# USB-UART.net
KiCad netlist of a schematic drawn in Altium Designer
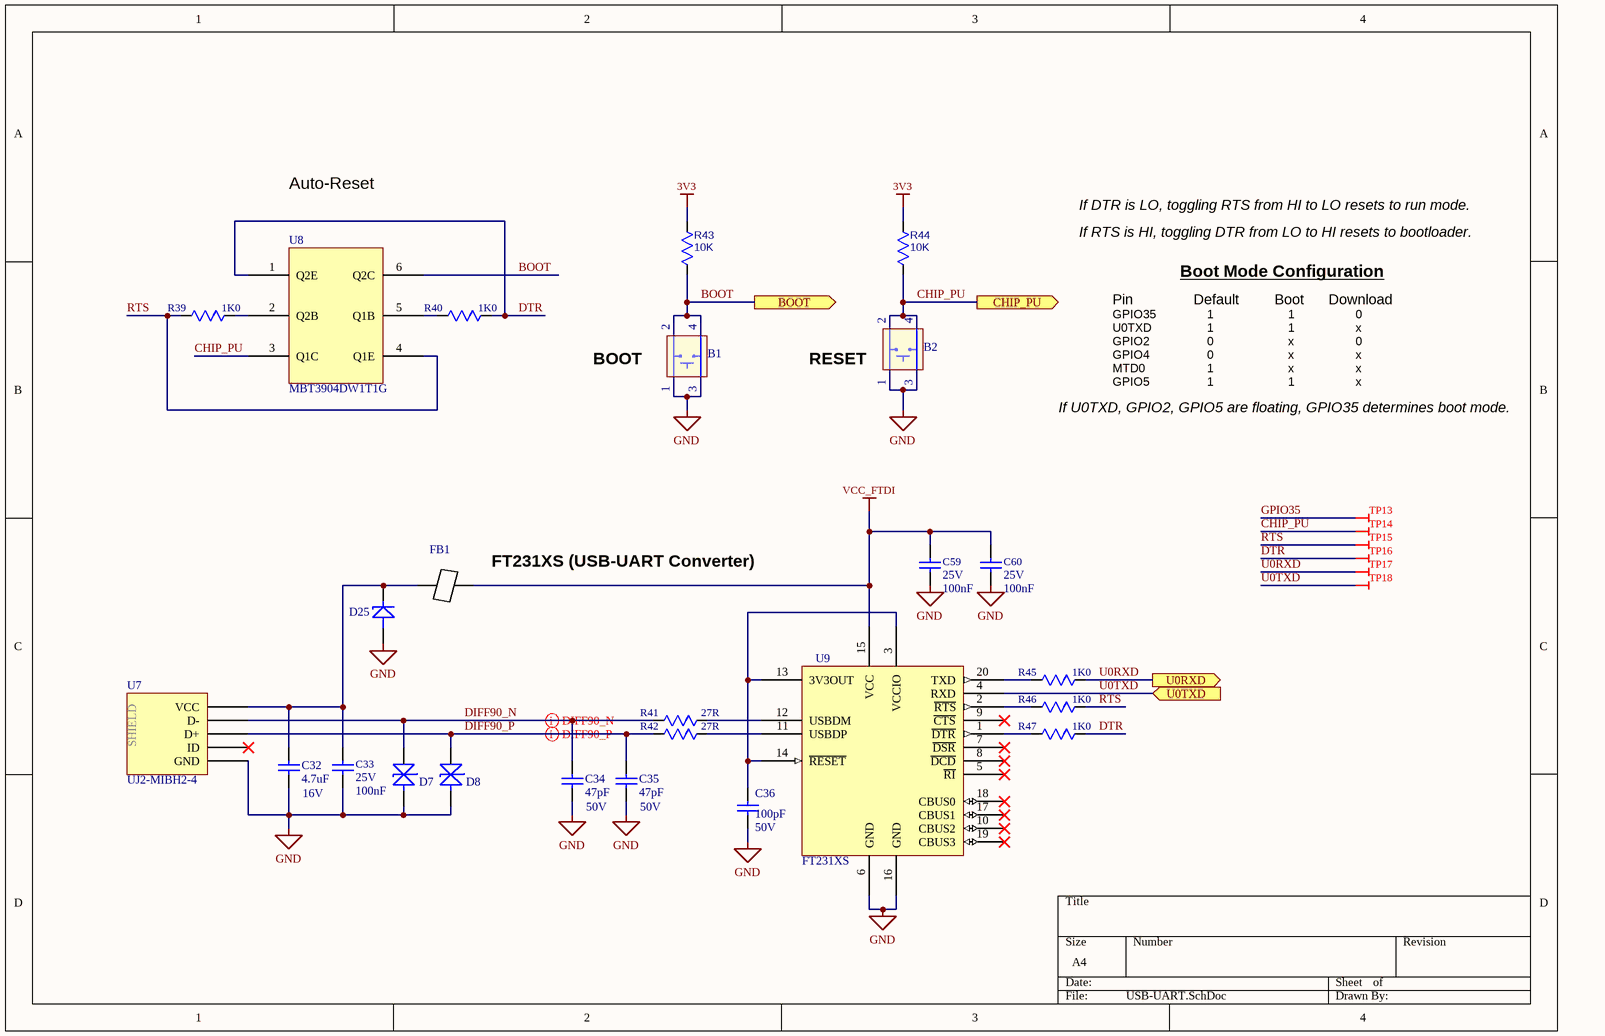
[diagram p0: USB-UART.SchDoc]

(export (version "E")
  (design (tool "Eeschema 10.0.6"))
  (components
    (comp (ref "B1")
      (value "Button C&K PTS815 SJG 250 SMTR LFS")
      (footprint "PTS 815")
      (description "Push Button Top")
      (fields
        (field (name "MANUFACTURER") "C&K Components")
        (field (name "MANUFACTURER PART NUMBER") "PTS815 SJG 250 SMTR LFS")
      )
      (libsource (lib "Connectors") (part "Button C&K PTS815 SJG 250 SMTR LFS"))
    )
    (comp (ref "B2")
      (value "Button C&K PTS815 SJG 250 SMTR LFS")
      (footprint "PTS 815")
      (description "Push Button Top")
      (fields
        (field (name "MANUFACTURER") "C&K Components")
        (field (name "MANUFACTURER PART NUMBER") "PTS815 SJG 250 SMTR LFS")
      )
      (libsource (lib "Connectors") (part "Button C&K PTS815 SJG 250 SMTR LFS"))
    )
    (comp (ref "C32")
      (value "4.7uF")
      (footprint "C1005[0402]")
      (description "Cap,4.7uF,10V,20%,X5R,0402")
      (fields
        (field (name "MANUFACTURER") "Samsung Electro-Mechanics")
        (field (name "MANUFACTURER PART NUMBER") "CL05A475MO5NUNC")
        (field (name "VOLTAGE") "16V")
      )
      (libsource (lib "Capacitors") (part "4.7uF_0402_10V"))
    )
    (comp (ref "C33")
      (value "100nF")
      (footprint "CAPC1005X06N")
      (fields
        (field (name "VOLTAGE") "25V")
        (field (name "MANUFACTURER PART NUMBER") "CL05A104KA5NNNC")
        (field (name "MANUFACTURER") "Samsung")
        (field (name "Comment") "4.7uF")
      )
      (libsource (lib "Capacitors") (part "4.7uF_0603_10V"))
    )
    (comp (ref "C34")
      (value "47pF")
      (footprint "C1005[0402]")
      (description "Cap,47pF,50V,5%,C0G/NP0")
      (fields
        (field (name "MANUFACTURER") "Yageo")
        (field (name "MANUFACTURER PART NUMBER") "CC0402JRNPO9BN470")
        (field (name "VOLTAGE") "50V")
      )
      (libsource (lib "Capacitors") (part "47pF_0402_50V"))
    )
    (comp (ref "C35")
      (value "47pF")
      (footprint "C1005[0402]")
      (description "Cap,47pF,50V,5%,C0G/NP0")
      (fields
        (field (name "MANUFACTURER PART NUMBER") "CC0402JRNPO9BN470")
        (field (name "MANUFACTURER") "Yageo")
        (field (name "VOLTAGE") "50V")
      )
      (libsource (lib "Capacitors") (part "47pF_0402_50V"))
    )
    (comp (ref "C36")
      (value "100pF")
      (footprint "C1005[0402]")
      (description "Cap,100pF,10V,5%,C0G/NP0,0402")
      (fields
        (field (name "MANUFACTURER PART NUMBER") "CC0402JRNPO9BN101")
        (field (name "MANUFACTURER") "Yageo")
        (field (name "VOLTAGE") "50V")
      )
      (libsource (lib "Capacitors") (part "100pF_0402_10V"))
    )
    (comp (ref "C59")
      (value "100nF")
      (footprint "CAPC1005X06N")
      (fields
        (field (name "VOLTAGE") "25V")
        (field (name "MANUFACTURER PART NUMBER") "CL05A104KA5NNNC")
        (field (name "MANUFACTURER") "Samsung")
        (field (name "Comment") "4.7uF")
      )
      (libsource (lib "Capacitors") (part "4.7uF_0603_10V"))
    )
    (comp (ref "C60")
      (value "100nF")
      (footprint "CAPC1005X06N")
      (fields
        (field (name "VOLTAGE") "25V")
        (field (name "MANUFACTURER PART NUMBER") "CL05A104KA5NNNC")
        (field (name "MANUFACTURER") "Samsung")
        (field (name "Comment") "4.7uF")
      )
      (libsource (lib "Capacitors") (part "4.7uF_0603_10V"))
    )
    (comp (ref "D7")
      (value "ESD7951ST5GOSCT-ND")
      (footprint "SODFL100X40-2N")
      (description "TVS Diode")
      (fields
        (field (name "MANUFACTURER") "ON Semiconductor")
        (field (name "MANUFACTURER PART NUMBER") "ESD7951ST5G")
      )
      (libsource (lib "Gas Monitor Components") (part "ESD7951S"))
    )
    (comp (ref "D8")
      (value "ESD7951ST5GOSCT-ND")
      (footprint "SODFL100X40-2N")
      (description "TVS Diode")
      (fields
        (field (name "MANUFACTURER") "ON Semiconductor")
        (field (name "MANUFACTURER PART NUMBER") "ESD7951ST5G")
      )
      (libsource (lib "Gas Monitor Components") (part "ESD7951S"))
    )
    (comp (ref "D25")
      (value "5V TVS")
      (footprint "NXP PTVSxS1UR-Series (SOD123W)")
      (fields
        (field (name "MANUFACTURER") "Nexperia")
        (field (name "MANUFACTURER PART NUMBER") "PTVS5V0S1UR,115")
      )
      (libsource (lib "FSM_2018") (part "NXP PTVSxS1UR-Series"))
    )
    (comp (ref "FB1")
      (value "Ferrite Bead")
      (footprint "MI0805K400R-10")
      (description "MI0805K400R-10")
      (fields (field (name "MANUFACTURER") "Laird"))
      (libsource (lib "Gas Monitor Components") (part "Ferrite Bead"))
    )
    (comp (ref "R39")
      (value "1K0")
      (footprint "RESC1005X03N")
      (description "RES 1K Ohm ±5%, 0.25W,1/4W 0603")
      (fields
        (field (name "MANUFACTURER") "Panasonic")
        (field (name "MANUFACTURER PART NUMBER") "ERJ-2RKF1001X")
      )
      (libsource (lib "Resistors") (part "1K00_0603_0.1W"))
    )
    (comp (ref "R40")
      (value "1K0")
      (footprint "RESC1005X03N")
      (description "RES 1K Ohm ±5%, 0.25W,1/4W 0603")
      (fields
        (field (name "MANUFACTURER") "Panasonic")
        (field (name "MANUFACTURER PART NUMBER") "ERJ-2RKF1001X")
      )
      (libsource (lib "Resistors") (part "1K00_0603_0.1W"))
    )
    (comp (ref "R41")
      (value "27R")
      (footprint "RESC1005X03N")
      (description "RES 1K Ohm ±5%, 0.25W,1/4W 0603")
      (fields
        (field (name "MANUFACTURER") "Panasonic")
        (field (name "MANUFACTURER PART NUMBER") "ERJ-2GEJ270X")
      )
      (libsource (lib "Resistors") (part "1K00_0603_0.1W"))
    )
    (comp (ref "R42")
      (value "27R")
      (footprint "RESC1005X03N")
      (description "RES 1K Ohm ±5%, 0.25W,1/4W 0603")
      (fields
        (field (name "MANUFACTURER") "Panasonic")
        (field (name "MANUFACTURER PART NUMBER") "ERJ-2GEJ270X")
      )
      (libsource (lib "Resistors") (part "1K00_0603_0.1W"))
    )
    (comp (ref "R43")
      (value "10K")
      (footprint "RESC1005X03N")
      (description "RES 1K Ohm ±5%, 0.25W,1/4W 0603")
      (fields
        (field (name "MANUFACTURER") "Panasonic")
        (field (name "MANUFACTURER PART NUMBER") "ERJ-2RKF1002X")
      )
      (libsource (lib "Resistors") (part "1K00_0603_0.1W"))
    )
    (comp (ref "R44")
      (value "10K")
      (footprint "RESC1005X03N")
      (description "RES 1K Ohm ±5%, 0.25W,1/4W 0603")
      (fields
        (field (name "MANUFACTURER") "Panasonic")
        (field (name "MANUFACTURER PART NUMBER") "ERJ-2RKF1002X")
      )
      (libsource (lib "Resistors") (part "1K00_0603_0.1W"))
    )
    (comp (ref "R45")
      (value "1K0")
      (footprint "RESC1005X03N")
      (description "RES 1K Ohm ±5%, 0.25W,1/4W 0603")
      (fields
        (field (name "MANUFACTURER") "Panasonic")
        (field (name "MANUFACTURER PART NUMBER") "ERJ-2RKF1001X")
      )
      (libsource (lib "Resistors") (part "1K00_0603_0.1W"))
    )
    (comp (ref "R46")
      (value "1K0")
      (footprint "RESC1005X03N")
      (description "RES 1K Ohm ±5%, 0.25W,1/4W 0603")
      (fields
        (field (name "MANUFACTURER") "Panasonic")
        (field (name "MANUFACTURER PART NUMBER") "ERJ-2RKF1001X")
      )
      (libsource (lib "Resistors") (part "1K00_0603_0.1W"))
    )
    (comp (ref "R47")
      (value "1K0")
      (footprint "RESC1005X03N")
      (description "RES 1K Ohm ±5%, 0.25W,1/4W 0603")
      (fields
        (field (name "MANUFACTURER") "Panasonic")
        (field (name "MANUFACTURER PART NUMBER") "ERJ-2RKF1001X")
      )
      (libsource (lib "Resistors") (part "1K00_0603_0.1W"))
    )
    (comp (ref "TP13")
      (value "PAD")
      (footprint "TP_SMD_39MIL")
      (description "SMD Test Pad")
      (fields (field (name "MANUFACTURER") "No P/N Required"))
      (libsource (lib "Connectors") (part "TP_SMD_39MIL"))
    )
    (comp (ref "TP14")
      (value "PAD")
      (footprint "TP_SMD_39MIL")
      (description "SMD Test Pad")
      (fields (field (name "MANUFACTURER") "No P/N Required"))
      (libsource (lib "Connectors") (part "TP_SMD_39MIL"))
    )
    (comp (ref "TP15")
      (value "PAD")
      (footprint "TP_SMD_39MIL")
      (description "SMD Test Pad")
      (fields (field (name "MANUFACTURER") "No P/N Required"))
      (libsource (lib "Connectors") (part "TP_SMD_39MIL"))
    )
    (comp (ref "TP16")
      (value "PAD")
      (footprint "TP_SMD_39MIL")
      (description "SMD Test Pad")
      (fields (field (name "MANUFACTURER") "No P/N Required"))
      (libsource (lib "Connectors") (part "TP_SMD_39MIL"))
    )
    (comp (ref "TP17")
      (value "PAD")
      (footprint "TP_SMD_39MIL")
      (description "SMD Test Pad")
      (fields (field (name "MANUFACTURER") "No P/N Required"))
      (libsource (lib "Connectors") (part "TP_SMD_39MIL"))
    )
    (comp (ref "TP18")
      (value "PAD")
      (footprint "TP_SMD_39MIL")
      (description "SMD Test Pad")
      (fields (field (name "MANUFACTURER") "No P/N Required"))
      (libsource (lib "Connectors") (part "TP_SMD_39MIL"))
    )
    (comp (ref "U7")
      (value "UJ2-MIBH2-4")
      (footprint "UJ2-MIBH2-4-SMT")
      (fields
        (field (name "MANUFACTURER") "CUI")
        (field (name "MANUFACTURER PART NUMBER") "UJ2-MIBH2-4-SMT-TR")
      )
      (libsource (lib "Gas Monitor Components") (part "USB Shield"))
    )
    (comp (ref "U8")
      (value "MBT3904DW1T1G")
      (footprint "SOT65P210X110-6N")
      (description "Dual NPN Transistors")
      (fields
        (field (name "MANUFACTURER") "ON Semiconductor")
        (field (name "MANUFACTURER PART NUMBER") "SMBT3904DW1T1G")
      )
      (libsource (lib "Gas Monitor Components") (part "MBT3904DW1"))
    )
    (comp (ref "U9")
      (value "FT231XS")
      (footprint "SOP64P1030X175-20N")
      (description "USB-UART Interface")
      (fields (field (name "MANUFACTURER") "FTDI") (field (name "MANUFACTURER PART NUMBER") "FT231XS-R"))
      (libsource (lib "Gas Monitor Components") (part "FT231XS"))
    )
  )
  (nets
    (net (code "1") (name "/BOOT") (class "Default")
      (node (ref "B1") (pin "2") (pinfunction "2_2") (pintype "passive"))
      (node (ref "B1") (pin "4") (pinfunction "4_4") (pintype "passive"))
      (node (ref "R43") (pin "1") (pintype "passive"))
      (node (ref "U8") (pin "6") (pinfunction "Q2C_6") (pintype "passive"))
    )
    (net (code "2") (name "/CHIP_PU") (class "Default")
      (node (ref "B2") (pin "2") (pinfunction "2_2") (pintype "passive"))
      (node (ref "B2") (pin "4") (pinfunction "4_4") (pintype "passive"))
      (node (ref "R44") (pin "1") (pintype "passive"))
      (node (ref "TP14") (pin "1") (pintype "passive"))
      (node (ref "U8") (pin "3") (pinfunction "Q1C_3") (pintype "passive"))
    )
    (net (code "3") (name "/DIFF90_N") (class "Default")
      (node (ref "C34") (pin "2") (pintype "passive"))
      (node (ref "D7") (pin "2") (pinfunction "ANODE_2") (pintype "passive"))
      (node (ref "R41") (pin "2") (pintype "passive"))
      (node (ref "U7") (pin "2") (pinfunction "D-_2") (pintype "passive"))
    )
    (net (code "4") (name "/DIFF90_P") (class "Default")
      (node (ref "C35") (pin "2") (pintype "passive"))
      (node (ref "D8") (pin "2") (pinfunction "ANODE_2") (pintype "passive"))
      (node (ref "R42") (pin "2") (pintype "passive"))
      (node (ref "U7") (pin "3") (pinfunction "D+_3") (pintype "passive"))
    )
    (net (code "5") (name "/DTR") (class "Default")
      (node (ref "R40") (pin "2") (pintype "passive"))
      (node (ref "R47") (pin "2") (pintype "passive"))
      (node (ref "TP16") (pin "1") (pintype "passive"))
      (node (ref "U8") (pin "1") (pinfunction "Q2E_1") (pintype "passive"))
    )
    (net (code "6") (name "/GPIO35") (class "Default") (node (ref "TP13") (pin "1") (pintype "passive")))
    (net (code "7") (name "/RTS") (class "Default")
      (node (ref "R39") (pin "1") (pintype "passive"))
      (node (ref "R46") (pin "2") (pintype "passive"))
      (node (ref "TP15") (pin "1") (pintype "passive"))
      (node (ref "U8") (pin "4") (pinfunction "Q1E_4") (pintype "passive"))
    )
    (net (code "8") (name "/U0RXD") (class "Default")
      (node (ref "R45") (pin "2") (pintype "passive"))
      (node (ref "TP17") (pin "1") (pintype "passive"))
    )
    (net (code "9") (name "/U0TXD") (class "Default")
      (node (ref "TP18") (pin "1") (pintype "passive"))
      (node (ref "U9") (pin "4") (pinfunction "RXD_4") (pintype "passive"))
    )
    (net (code "10") (name "3V3") (class "Default")
      (node (ref "R43") (pin "2") (pintype "passive"))
      (node (ref "R44") (pin "2") (pintype "passive"))
    )
    (net (code "11") (name "GND") (class "Default")
      (node (ref "B1") (pin "1") (pinfunction "1_1") (pintype "passive"))
      (node (ref "B1") (pin "3") (pinfunction "3_3") (pintype "passive"))
      (node (ref "B2") (pin "1") (pinfunction "1_1") (pintype "passive"))
      (node (ref "B2") (pin "3") (pinfunction "3_3") (pintype "passive"))
      (node (ref "C32") (pin "1") (pintype "passive"))
      (node (ref "C33") (pin "2") (pintype "passive"))
      (node (ref "C34") (pin "1") (pintype "passive"))
      (node (ref "C35") (pin "1") (pintype "passive"))
      (node (ref "C36") (pin "1") (pintype "passive"))
      (node (ref "C59") (pin "2") (pintype "passive"))
      (node (ref "C60") (pin "2") (pintype "passive"))
      (node (ref "D25") (pin "2") (pinfunction "2_2") (pintype "passive"))
      (node (ref "D7") (pin "1") (pinfunction "CATHODE_1") (pintype "passive"))
      (node (ref "D8") (pin "1") (pinfunction "CATHODE_1") (pintype "passive"))
      (node (ref "U7") (pin "5") (pinfunction "GND_5") (pintype "power_in"))
      (node (ref "U9") (pin "16") (pinfunction "GND_16") (pintype "power_in"))
      (node (ref "U9") (pin "6") (pinfunction "GND_6") (pintype "power_in"))
    )
    (net (code "12") (name "Net-(U7-VCC)") (class "Default")
      (node (ref "C32") (pin "2") (pintype "passive"))
      (node (ref "C33") (pin "1") (pintype "passive"))
      (node (ref "D25") (pin "1") (pinfunction "1_1") (pintype "passive"))
      (node (ref "FB1") (pin "1") (pinfunction "1_1") (pintype "passive"))
      (node (ref "U7") (pin "1") (pinfunction "VCC_1") (pintype "power_in"))
    )
    (net (code "13") (name "Net-(U8-Q1B)") (class "Default")
      (node (ref "R40") (pin "1") (pintype "passive"))
      (node (ref "U8") (pin "5") (pinfunction "Q1B_5") (pintype "passive"))
    )
    (net (code "14") (name "Net-(U8-Q2B)") (class "Default")
      (node (ref "R39") (pin "2") (pintype "passive"))
      (node (ref "U8") (pin "2") (pinfunction "Q2B_2") (pintype "passive"))
    )
    (net (code "15") (name "Net-(U9-3V3OUT)") (class "Default")
      (node (ref "C36") (pin "2") (pintype "passive"))
      (node (ref "U9") (pin "13") (pinfunction "3V3OUT_13") (pintype "power_in"))
      (node (ref "U9") (pin "14") (pinfunction "~{RESET}_14") (pintype "input"))
      (node (ref "U9") (pin "3") (pinfunction "VCCIO_3") (pintype "passive"))
    )
    (net (code "16") (name "Net-(U9-TXD)") (class "Default")
      (node (ref "R45") (pin "1") (pintype "passive"))
      (node (ref "U9") (pin "20") (pinfunction "TXD_20") (pintype "output"))
    )
    (net (code "17") (name "Net-(U9-USBDM)") (class "Default")
      (node (ref "R41") (pin "1") (pintype "passive"))
      (node (ref "U9") (pin "12") (pinfunction "USBDM_12") (pintype "passive"))
    )
    (net (code "18") (name "Net-(U9-USBDP)") (class "Default")
      (node (ref "R42") (pin "1") (pintype "passive"))
      (node (ref "U9") (pin "11") (pinfunction "USBDP_11") (pintype "passive"))
    )
    (net (code "19") (name "Net-(U9-~{DTR})") (class "Default")
      (node (ref "R47") (pin "1") (pintype "passive"))
      (node (ref "U9") (pin "1") (pinfunction "~{DTR}_1") (pintype "output"))
    )
    (net (code "20") (name "Net-(U9-~{RTS})") (class "Default")
      (node (ref "R46") (pin "1") (pintype "passive"))
      (node (ref "U9") (pin "2") (pinfunction "~{RTS}_2") (pintype "output"))
    )
    (net (code "21") (name "VCC_FTDI") (class "Default")
      (node (ref "C59") (pin "1") (pintype "passive"))
      (node (ref "C60") (pin "1") (pintype "passive"))
      (node (ref "FB1") (pin "2") (pinfunction "2_2") (pintype "passive"))
      (node (ref "U9") (pin "15") (pinfunction "VCC_15") (pintype "power_in"))
    )
    (net (code "22") (name "unconnected-(U7-ID-Pad4)") (class "Default")
      (node (ref "U7") (pin "4") (pinfunction "ID_4") (pintype "passive+no_connect"))
    )
    (net (code "23") (name "unconnected-(U9-CBUS0-Pad18)") (class "Default")
      (node (ref "U9") (pin "18") (pinfunction "CBUS0_18") (pintype "bidirectional+no_connect"))
    )
    (net (code "24") (name "unconnected-(U9-CBUS1-Pad17)") (class "Default")
      (node (ref "U9") (pin "17") (pinfunction "CBUS1_17") (pintype "bidirectional+no_connect"))
    )
    (net (code "25") (name "unconnected-(U9-CBUS2-Pad10)") (class "Default")
      (node (ref "U9") (pin "10") (pinfunction "CBUS2_10") (pintype "bidirectional+no_connect"))
    )
    (net (code "26") (name "unconnected-(U9-CBUS3-Pad19)") (class "Default")
      (node (ref "U9") (pin "19") (pinfunction "CBUS3_19") (pintype "bidirectional+no_connect"))
    )
    (net (code "27") (name "unconnected-(U9-~{CTS}-Pad9)") (class "Default")
      (node (ref "U9") (pin "9") (pinfunction "~{CTS}_9") (pintype "passive+no_connect"))
    )
    (net (code "28") (name "unconnected-(U9-~{DCD}-Pad8)") (class "Default")
      (node (ref "U9") (pin "8") (pinfunction "~{DCD}_8") (pintype "passive+no_connect"))
    )
    (net (code "29") (name "unconnected-(U9-~{DSR}-Pad7)") (class "Default")
      (node (ref "U9") (pin "7") (pinfunction "~{DSR}_7") (pintype "passive+no_connect"))
    )
    (net (code "30") (name "unconnected-(U9-~{RI}-Pad5)") (class "Default")
      (node (ref "U9") (pin "5") (pinfunction "~{RI}_5") (pintype "passive+no_connect"))
    )
  )
)
